# DL110.net
KiCad netlist of a schematic drawn in EAGLE
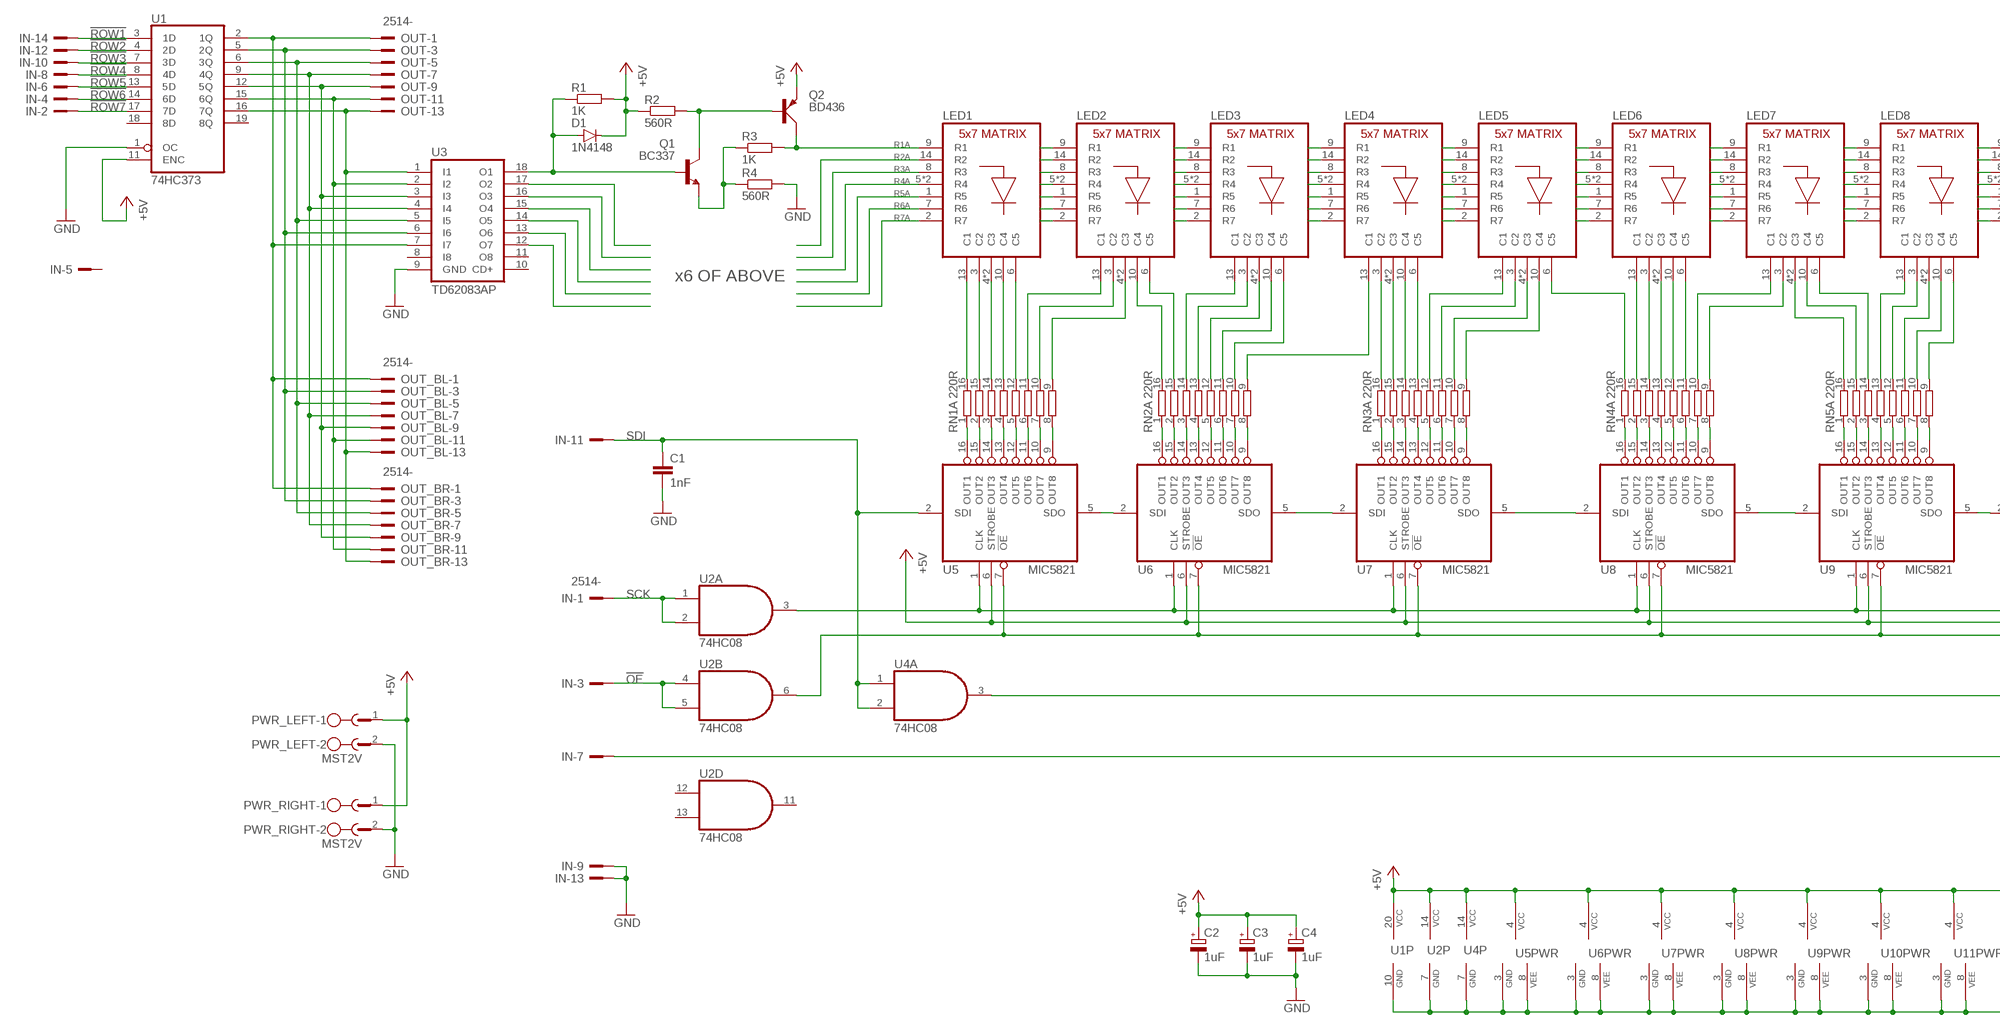
[diagram p0: schematic, sheet 1, part 1 of 2]
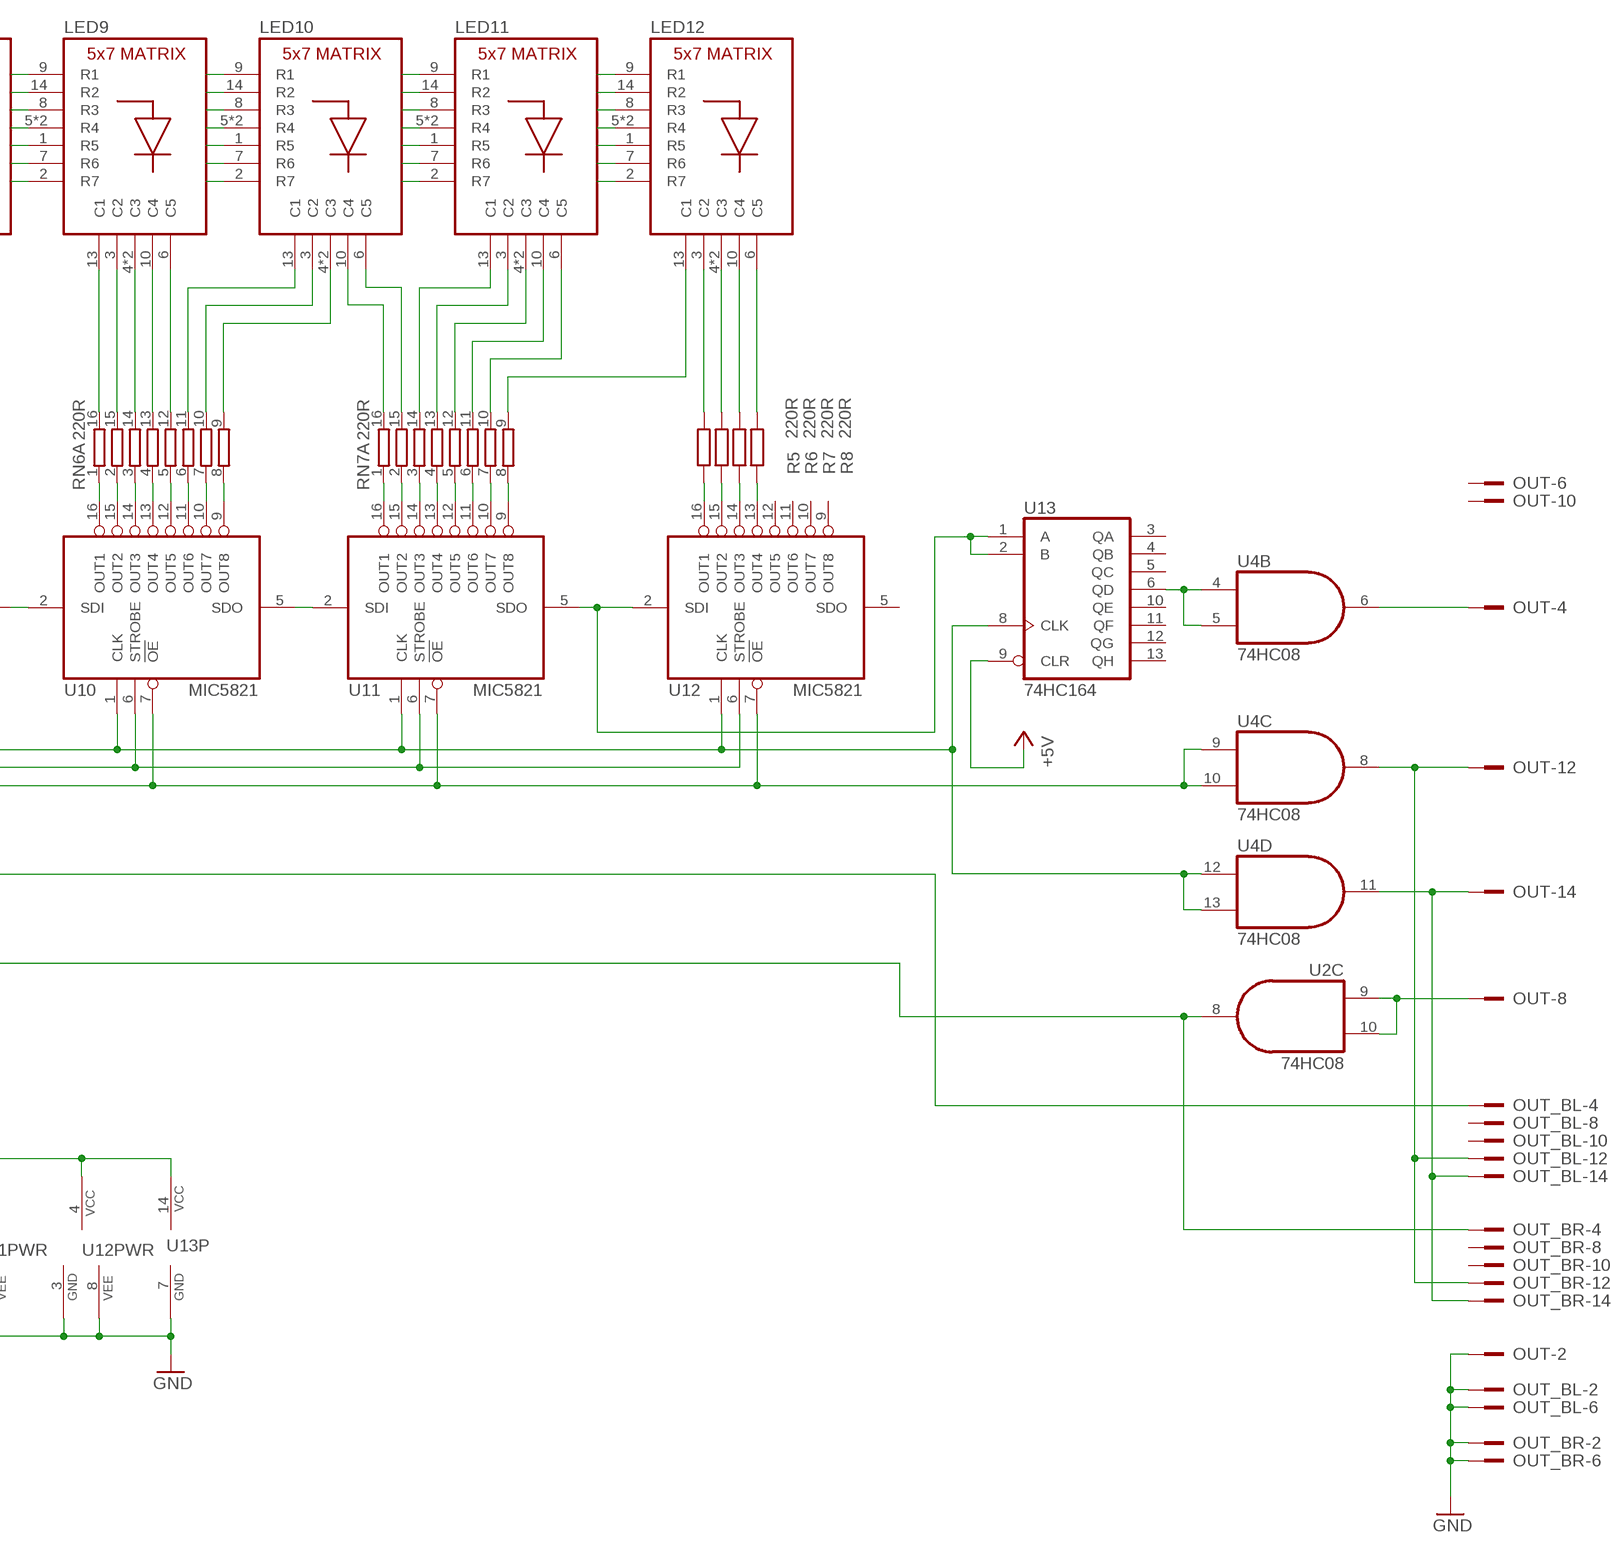
[diagram p1: schematic, sheet 1, part 2 of 2]

(export (version "E")
  (design (tool "Eeschema 10.0.6"))
  (components
    (comp (ref "C1")
      (value "1nF")
      (footprint "eagle-import:C050-025X075")
      (libsource (lib "eagle-import") (part "C-EU050-025X075"))
    )
    (comp (ref "C2")
      (value "1uF")
      (footprint "eagle-import:E2,5-5")
      (libsource (lib "eagle-import") (part "CPOL-EUE2.5-5"))
    )
    (comp (ref "C3")
      (value "1uF")
      (footprint "eagle-import:E2,5-5")
      (libsource (lib "eagle-import") (part "CPOL-EUE2.5-5"))
    )
    (comp (ref "C4")
      (value "1uF")
      (footprint "eagle-import:E2,5-5")
      (libsource (lib "eagle-import") (part "CPOL-EUE2.5-5"))
    )
    (comp (ref "D1")
      (value "1N4148")
      (footprint "eagle-import:DO35-10")
      (libsource (lib "eagle-import") (part "1N4148DO35-10"))
    )
    (comp (ref "IN")
      (value "2514-")
      (footprint "eagle-import:PAK100_2500-14")
      (libsource (lib "eagle-import") (part "2514-"))
    )
    (comp (ref "LED1")
      (value "CSM-57141")
      (footprint "eagle-import:CSM-57141")
      (libsource (lib "eagle-import") (part "CSM-57141"))
    )
    (comp (ref "LED2")
      (value "CSM-57141")
      (footprint "eagle-import:CSM-57141")
      (libsource (lib "eagle-import") (part "CSM-57141"))
    )
    (comp (ref "LED3")
      (value "CSM-57141")
      (footprint "eagle-import:CSM-57141")
      (libsource (lib "eagle-import") (part "CSM-57141"))
    )
    (comp (ref "LED4")
      (value "CSM-57141")
      (footprint "eagle-import:CSM-57141")
      (libsource (lib "eagle-import") (part "CSM-57141"))
    )
    (comp (ref "LED5")
      (value "CSM-57141")
      (footprint "eagle-import:CSM-57141")
      (libsource (lib "eagle-import") (part "CSM-57141"))
    )
    (comp (ref "LED6")
      (value "CSM-57141")
      (footprint "eagle-import:CSM-57141")
      (libsource (lib "eagle-import") (part "CSM-57141"))
    )
    (comp (ref "LED7")
      (value "CSM-57141")
      (footprint "eagle-import:CSM-57141")
      (libsource (lib "eagle-import") (part "CSM-57141"))
    )
    (comp (ref "LED8")
      (value "CSM-57141")
      (footprint "eagle-import:CSM-57141")
      (libsource (lib "eagle-import") (part "CSM-57141"))
    )
    (comp (ref "LED9")
      (value "CSM-57141")
      (footprint "eagle-import:CSM-57141")
      (libsource (lib "eagle-import") (part "CSM-57141"))
    )
    (comp (ref "LED10")
      (value "CSM-57141")
      (footprint "eagle-import:CSM-57141")
      (libsource (lib "eagle-import") (part "CSM-57141"))
    )
    (comp (ref "LED11")
      (value "CSM-57141")
      (footprint "eagle-import:CSM-57141")
      (libsource (lib "eagle-import") (part "CSM-57141"))
    )
    (comp (ref "LED12")
      (value "CSM-57141")
      (footprint "eagle-import:CSM-57141")
      (libsource (lib "eagle-import") (part "CSM-57141"))
    )
    (comp (ref "OUT")
      (value "2514-")
      (footprint "eagle-import:PAK100_2500-14")
      (fields (field (name "SPICEPREFIX") "X"))
      (libsource (lib "eagle-import") (part "2514-"))
    )
    (comp (ref "OUT_BL")
      (value "2514-")
      (footprint "eagle-import:PAK100_2500-14")
      (libsource (lib "eagle-import") (part "2514-"))
    )
    (comp (ref "OUT_BR")
      (value "2514-")
      (footprint "eagle-import:PAK100_2500-14")
      (libsource (lib "eagle-import") (part "2514-"))
    )
    (comp (ref "PWR_LEFT")
      (value "MST2V")
      (footprint "eagle-import:MSTBV2")
      (libsource (lib "eagle-import") (part "MST2V"))
    )
    (comp (ref "PWR_RIGHT")
      (value "MST2V")
      (footprint "eagle-import:MSTBV2")
      (libsource (lib "eagle-import") (part "MST2V"))
    )
    (comp (ref "Q1")
      (value "BC337")
      (footprint "eagle-import:TO92")
      (libsource (lib "eagle-import") (part "BC337"))
    )
    (comp (ref "Q2")
      (value "BD436")
      (footprint "eagle-import:TO126AV")
      (libsource (lib "eagle-import") (part "BD438"))
    )
    (comp (ref "R1")
      (value "1K")
      (footprint "eagle-import:0207_10")
      (libsource (lib "eagle-import") (part "R-EU_0207/10"))
    )
    (comp (ref "R2")
      (value "560R")
      (footprint "eagle-import:0207_10")
      (libsource (lib "eagle-import") (part "R-EU_0207/10"))
    )
    (comp (ref "R3")
      (value "1K")
      (footprint "eagle-import:0207_10")
      (libsource (lib "eagle-import") (part "R-EU_0207/10"))
    )
    (comp (ref "R4")
      (value "560R")
      (footprint "eagle-import:0207_10")
      (libsource (lib "eagle-import") (part "R-EU_0207/10"))
    )
    (comp (ref "R5")
      (value "220R")
      (footprint "eagle-import:0207_10")
      (libsource (lib "eagle-import") (part "R-EU_0207/10"))
    )
    (comp (ref "R6")
      (value "220R")
      (footprint "eagle-import:0207_10")
      (libsource (lib "eagle-import") (part "R-EU_0207/10"))
    )
    (comp (ref "R7")
      (value "220R")
      (footprint "eagle-import:0207_10")
      (libsource (lib "eagle-import") (part "R-EU_0207/10"))
    )
    (comp (ref "R8")
      (value "220R")
      (footprint "eagle-import:0207_10")
      (libsource (lib "eagle-import") (part "R-EU_0207/10"))
    )
    (comp (ref "RN1")
      (value "220R")
      (footprint "eagle-import:DIL16")
      (libsource (lib "eagle-import") (part "8R-N"))
    )
    (comp (ref "RN2")
      (value "220R")
      (footprint "eagle-import:DIL16")
      (libsource (lib "eagle-import") (part "8R-N"))
    )
    (comp (ref "RN3")
      (value "220R")
      (footprint "eagle-import:DIL16")
      (libsource (lib "eagle-import") (part "8R-N"))
    )
    (comp (ref "RN4")
      (value "220R")
      (footprint "eagle-import:DIL16")
      (libsource (lib "eagle-import") (part "8R-N"))
    )
    (comp (ref "RN5")
      (value "220R")
      (footprint "eagle-import:DIL16")
      (libsource (lib "eagle-import") (part "8R-N"))
    )
    (comp (ref "RN6")
      (value "220R")
      (footprint "eagle-import:DIL16")
      (libsource (lib "eagle-import") (part "8R-N"))
    )
    (comp (ref "RN7")
      (value "220R")
      (footprint "eagle-import:DIL16")
      (libsource (lib "eagle-import") (part "8R-N"))
    )
    (comp (ref "U1")
      (value "74HC373")
      (footprint "eagle-import:DIL20")
      (libsource (lib "eagle-import") (part "74373NLS"))
    )
    (comp (ref "U2")
      (value "74HC08")
      (footprint "eagle-import:DIL14")
      (libsource (lib "eagle-import") (part "7408NLS"))
    )
    (comp (ref "U3")
      (value "TD62083AP")
      (footprint "eagle-import:DIL18")
      (libsource (lib "eagle-import") (part "ULN2803A"))
    )
    (comp (ref "U4")
      (value "74HC08")
      (footprint "eagle-import:DIL14")
      (libsource (lib "eagle-import") (part "7408NLS"))
    )
    (comp (ref "U5")
      (value "MIC5821")
      (footprint "eagle-import:DIL16")
      (libsource (lib "eagle-import") (part "MIC5821BN"))
    )
    (comp (ref "U6")
      (value "MIC5821")
      (footprint "eagle-import:DIL16")
      (libsource (lib "eagle-import") (part "MIC5821BN"))
    )
    (comp (ref "U7")
      (value "MIC5821")
      (footprint "eagle-import:DIL16")
      (libsource (lib "eagle-import") (part "MIC5821BN"))
    )
    (comp (ref "U8")
      (value "MIC5821")
      (footprint "eagle-import:DIL16")
      (libsource (lib "eagle-import") (part "MIC5821BN"))
    )
    (comp (ref "U9")
      (value "MIC5821")
      (footprint "eagle-import:DIL16")
      (libsource (lib "eagle-import") (part "MIC5821BN"))
    )
    (comp (ref "U10")
      (value "MIC5821")
      (footprint "eagle-import:DIL16")
      (libsource (lib "eagle-import") (part "MIC5821BN"))
    )
    (comp (ref "U11")
      (value "MIC5821")
      (footprint "eagle-import:DIL16")
      (libsource (lib "eagle-import") (part "MIC5821BN"))
    )
    (comp (ref "U12")
      (value "MIC5821")
      (footprint "eagle-import:DIL16")
      (libsource (lib "eagle-import") (part "MIC5821BN"))
    )
    (comp (ref "U13")
      (value "74HC164")
      (footprint "eagle-import:DIL14")
      (libsource (lib "eagle-import") (part "74164NLS"))
    )
  )
  (nets
    (net (code "1") (name "+5V") (class "Default")
      (node (ref "C2") (pin "+") (pinfunction "+_+") (pintype "passive"))
      (node (ref "C3") (pin "+") (pinfunction "+_+") (pintype "passive"))
      (node (ref "C4") (pin "+") (pinfunction "+_+") (pintype "passive"))
      (node (ref "D1") (pin "C") (pinfunction "C_C") (pintype "passive"))
      (node (ref "PWR_LEFT") (pin "1") (pinfunction "1_1") (pintype "passive"))
      (node (ref "PWR_RIGHT") (pin "1") (pinfunction "1_1") (pintype "passive"))
      (node (ref "Q2") (pin "E") (pinfunction "E_E") (pintype "passive"))
      (node (ref "R1") (pin "2") (pinfunction "2_2") (pintype "passive"))
      (node (ref "R2") (pin "1") (pinfunction "1_1") (pintype "passive"))
      (node (ref "U1") (pin "11") (pinfunction "ENC_11") (pintype "input"))
      (node (ref "U1") (pin "20") (pinfunction "VCC_20") (pintype "power_in"))
      (node (ref "U10") (pin "4") (pinfunction "VCC_4") (pintype "power_in"))
      (node (ref "U10") (pin "6") (pinfunction "STROBE_6") (pintype "input"))
      (node (ref "U11") (pin "4") (pinfunction "VCC_4") (pintype "power_in"))
      (node (ref "U11") (pin "6") (pinfunction "STROBE_6") (pintype "input"))
      (node (ref "U12") (pin "4") (pinfunction "VCC_4") (pintype "power_in"))
      (node (ref "U12") (pin "6") (pinfunction "STROBE_6") (pintype "input"))
      (node (ref "U13") (pin "14") (pinfunction "VCC_14") (pintype "power_in"))
      (node (ref "U13") (pin "9") (pinfunction "CLR_9") (pintype "input"))
      (node (ref "U2") (pin "14") (pinfunction "VCC_14") (pintype "power_in"))
      (node (ref "U4") (pin "14") (pinfunction "VCC_14") (pintype "power_in"))
      (node (ref "U5") (pin "4") (pinfunction "VCC_4") (pintype "power_in"))
      (node (ref "U5") (pin "6") (pinfunction "STROBE_6") (pintype "input"))
      (node (ref "U6") (pin "4") (pinfunction "VCC_4") (pintype "power_in"))
      (node (ref "U6") (pin "6") (pinfunction "STROBE_6") (pintype "input"))
      (node (ref "U7") (pin "4") (pinfunction "VCC_4") (pintype "power_in"))
      (node (ref "U7") (pin "6") (pinfunction "STROBE_6") (pintype "input"))
      (node (ref "U8") (pin "4") (pinfunction "VCC_4") (pintype "power_in"))
      (node (ref "U8") (pin "6") (pinfunction "STROBE_6") (pintype "input"))
      (node (ref "U9") (pin "4") (pinfunction "VCC_4") (pintype "power_in"))
      (node (ref "U9") (pin "6") (pinfunction "STROBE_6") (pintype "input"))
    )
    (net (code "2") (name "/R1A") (class "Default")
      (node (ref "LED1") (pin "9") (pinfunction "R1_9") (pintype "input"))
      (node (ref "LED10") (pin "9") (pinfunction "R1_9") (pintype "input"))
      (node (ref "LED11") (pin "9") (pinfunction "R1_9") (pintype "input"))
      (node (ref "LED12") (pin "9") (pinfunction "R1_9") (pintype "input"))
      (node (ref "LED2") (pin "9") (pinfunction "R1_9") (pintype "input"))
      (node (ref "LED3") (pin "9") (pinfunction "R1_9") (pintype "input"))
      (node (ref "LED4") (pin "9") (pinfunction "R1_9") (pintype "input"))
      (node (ref "LED5") (pin "9") (pinfunction "R1_9") (pintype "input"))
      (node (ref "LED6") (pin "9") (pinfunction "R1_9") (pintype "input"))
      (node (ref "LED7") (pin "9") (pinfunction "R1_9") (pintype "input"))
      (node (ref "LED8") (pin "9") (pinfunction "R1_9") (pintype "input"))
      (node (ref "LED9") (pin "9") (pinfunction "R1_9") (pintype "input"))
      (node (ref "Q2") (pin "C") (pinfunction "C_C") (pintype "passive"))
      (node (ref "R3") (pin "2") (pinfunction "2_2") (pintype "passive"))
    )
    (net (code "3") (name "/R2A") (class "Default")
      (node (ref "LED1") (pin "14") (pinfunction "R2_14") (pintype "input"))
      (node (ref "LED10") (pin "14") (pinfunction "R2_14") (pintype "input"))
      (node (ref "LED11") (pin "14") (pinfunction "R2_14") (pintype "input"))
      (node (ref "LED12") (pin "14") (pinfunction "R2_14") (pintype "input"))
      (node (ref "LED2") (pin "14") (pinfunction "R2_14") (pintype "input"))
      (node (ref "LED3") (pin "14") (pinfunction "R2_14") (pintype "input"))
      (node (ref "LED4") (pin "14") (pinfunction "R2_14") (pintype "input"))
      (node (ref "LED5") (pin "14") (pinfunction "R2_14") (pintype "input"))
      (node (ref "LED6") (pin "14") (pinfunction "R2_14") (pintype "input"))
      (node (ref "LED7") (pin "14") (pinfunction "R2_14") (pintype "input"))
      (node (ref "LED8") (pin "14") (pinfunction "R2_14") (pintype "input"))
      (node (ref "LED9") (pin "14") (pinfunction "R2_14") (pintype "input"))
    )
    (net (code "4") (name "/R3A") (class "Default")
      (node (ref "LED1") (pin "8") (pinfunction "R3_8") (pintype "input"))
      (node (ref "LED10") (pin "8") (pinfunction "R3_8") (pintype "input"))
      (node (ref "LED11") (pin "8") (pinfunction "R3_8") (pintype "input"))
      (node (ref "LED12") (pin "8") (pinfunction "R3_8") (pintype "input"))
      (node (ref "LED2") (pin "8") (pinfunction "R3_8") (pintype "input"))
      (node (ref "LED3") (pin "8") (pinfunction "R3_8") (pintype "input"))
      (node (ref "LED4") (pin "8") (pinfunction "R3_8") (pintype "input"))
      (node (ref "LED5") (pin "8") (pinfunction "R3_8") (pintype "input"))
      (node (ref "LED6") (pin "8") (pinfunction "R3_8") (pintype "input"))
      (node (ref "LED7") (pin "8") (pinfunction "R3_8") (pintype "input"))
      (node (ref "LED8") (pin "8") (pinfunction "R3_8") (pintype "input"))
      (node (ref "LED9") (pin "8") (pinfunction "R3_8") (pintype "input"))
    )
    (net (code "5") (name "/R4A") (class "Default")
      (node (ref "LED1") (pin "12") (pinfunction "R4_12") (pintype "input"))
      (node (ref "LED1") (pin "5") (pinfunction "R4_5") (pintype "input"))
      (node (ref "LED10") (pin "12") (pinfunction "R4_12") (pintype "input"))
      (node (ref "LED10") (pin "5") (pinfunction "R4_5") (pintype "input"))
      (node (ref "LED11") (pin "12") (pinfunction "R4_12") (pintype "input"))
      (node (ref "LED11") (pin "5") (pinfunction "R4_5") (pintype "input"))
      (node (ref "LED12") (pin "12") (pinfunction "R4_12") (pintype "input"))
      (node (ref "LED12") (pin "5") (pinfunction "R4_5") (pintype "input"))
      (node (ref "LED2") (pin "12") (pinfunction "R4_12") (pintype "input"))
      (node (ref "LED2") (pin "5") (pinfunction "R4_5") (pintype "input"))
      (node (ref "LED3") (pin "12") (pinfunction "R4_12") (pintype "input"))
      (node (ref "LED3") (pin "5") (pinfunction "R4_5") (pintype "input"))
      (node (ref "LED4") (pin "12") (pinfunction "R4_12") (pintype "input"))
      (node (ref "LED4") (pin "5") (pinfunction "R4_5") (pintype "input"))
      (node (ref "LED5") (pin "12") (pinfunction "R4_12") (pintype "input"))
      (node (ref "LED5") (pin "5") (pinfunction "R4_5") (pintype "input"))
      (node (ref "LED6") (pin "12") (pinfunction "R4_12") (pintype "input"))
      (node (ref "LED6") (pin "5") (pinfunction "R4_5") (pintype "input"))
      (node (ref "LED7") (pin "12") (pinfunction "R4_12") (pintype "input"))
      (node (ref "LED7") (pin "5") (pinfunction "R4_5") (pintype "input"))
      (node (ref "LED8") (pin "12") (pinfunction "R4_12") (pintype "input"))
      (node (ref "LED8") (pin "5") (pinfunction "R4_5") (pintype "input"))
      (node (ref "LED9") (pin "12") (pinfunction "R4_12") (pintype "input"))
      (node (ref "LED9") (pin "5") (pinfunction "R4_5") (pintype "input"))
    )
    (net (code "6") (name "/R5A") (class "Default")
      (node (ref "LED1") (pin "1") (pinfunction "R5_1") (pintype "input"))
      (node (ref "LED10") (pin "1") (pinfunction "R5_1") (pintype "input"))
      (node (ref "LED11") (pin "1") (pinfunction "R5_1") (pintype "input"))
      (node (ref "LED12") (pin "1") (pinfunction "R5_1") (pintype "input"))
      (node (ref "LED2") (pin "1") (pinfunction "R5_1") (pintype "input"))
      (node (ref "LED3") (pin "1") (pinfunction "R5_1") (pintype "input"))
      (node (ref "LED4") (pin "1") (pinfunction "R5_1") (pintype "input"))
      (node (ref "LED5") (pin "1") (pinfunction "R5_1") (pintype "input"))
      (node (ref "LED6") (pin "1") (pinfunction "R5_1") (pintype "input"))
      (node (ref "LED7") (pin "1") (pinfunction "R5_1") (pintype "input"))
      (node (ref "LED8") (pin "1") (pinfunction "R5_1") (pintype "input"))
      (node (ref "LED9") (pin "1") (pinfunction "R5_1") (pintype "input"))
    )
    (net (code "7") (name "/R6A") (class "Default")
      (node (ref "LED1") (pin "7") (pinfunction "R6_7") (pintype "input"))
      (node (ref "LED10") (pin "7") (pinfunction "R6_7") (pintype "input"))
      (node (ref "LED11") (pin "7") (pinfunction "R6_7") (pintype "input"))
      (node (ref "LED12") (pin "7") (pinfunction "R6_7") (pintype "input"))
      (node (ref "LED2") (pin "7") (pinfunction "R6_7") (pintype "input"))
      (node (ref "LED3") (pin "7") (pinfunction "R6_7") (pintype "input"))
      (node (ref "LED4") (pin "7") (pinfunction "R6_7") (pintype "input"))
      (node (ref "LED5") (pin "7") (pinfunction "R6_7") (pintype "input"))
      (node (ref "LED6") (pin "7") (pinfunction "R6_7") (pintype "input"))
      (node (ref "LED7") (pin "7") (pinfunction "R6_7") (pintype "input"))
      (node (ref "LED8") (pin "7") (pinfunction "R6_7") (pintype "input"))
      (node (ref "LED9") (pin "7") (pinfunction "R6_7") (pintype "input"))
    )
    (net (code "8") (name "/R7A") (class "Default")
      (node (ref "LED1") (pin "2") (pinfunction "R7_2") (pintype "input"))
      (node (ref "LED10") (pin "2") (pinfunction "R7_2") (pintype "input"))
      (node (ref "LED11") (pin "2") (pinfunction "R7_2") (pintype "input"))
      (node (ref "LED12") (pin "2") (pinfunction "R7_2") (pintype "input"))
      (node (ref "LED2") (pin "2") (pinfunction "R7_2") (pintype "input"))
      (node (ref "LED3") (pin "2") (pinfunction "R7_2") (pintype "input"))
      (node (ref "LED4") (pin "2") (pinfunction "R7_2") (pintype "input"))
      (node (ref "LED5") (pin "2") (pinfunction "R7_2") (pintype "input"))
      (node (ref "LED6") (pin "2") (pinfunction "R7_2") (pintype "input"))
      (node (ref "LED7") (pin "2") (pinfunction "R7_2") (pintype "input"))
      (node (ref "LED8") (pin "2") (pinfunction "R7_2") (pintype "input"))
      (node (ref "LED9") (pin "2") (pinfunction "R7_2") (pintype "input"))
    )
    (net (code "9") (name "/SCK") (class "Default")
      (node (ref "IN") (pin "1") (pinfunction "KL_1") (pintype "passive"))
      (node (ref "U2") (pin "1") (pinfunction "I0_1") (pintype "input"))
      (node (ref "U2") (pin "2") (pinfunction "I1_2") (pintype "input"))
    )
    (net (code "10") (name "/SDI") (class "Default")
      (node (ref "C1") (pin "1") (pinfunction "1_1") (pintype "passive"))
      (node (ref "IN") (pin "11") (pinfunction "KL_11") (pintype "passive"))
      (node (ref "U4") (pin "1") (pinfunction "I0_1") (pintype "input"))
      (node (ref "U4") (pin "2") (pinfunction "I1_2") (pintype "input"))
      (node (ref "U5") (pin "2") (pinfunction "SDI_2") (pintype "input"))
    )
    (net (code "11") (name "/~{OE}") (class "Default")
      (node (ref "IN") (pin "3") (pinfunction "KL_3") (pintype "passive"))
      (node (ref "U2") (pin "4") (pinfunction "I0_4") (pintype "input"))
      (node (ref "U2") (pin "5") (pinfunction "I1_5") (pintype "input"))
    )
    (net (code "12") (name "/~{ROW1}") (class "Default")
      (node (ref "IN") (pin "14") (pinfunction "KL_14") (pintype "passive"))
      (node (ref "U1") (pin "3") (pinfunction "1D_3") (pintype "input"))
    )
    (net (code "13") (name "/~{ROW2}") (class "Default")
      (node (ref "IN") (pin "12") (pinfunction "KL_12") (pintype "passive"))
      (node (ref "U1") (pin "4") (pinfunction "2D_4") (pintype "input"))
    )
    (net (code "14") (name "/~{ROW3}") (class "Default")
      (node (ref "IN") (pin "10") (pinfunction "KL_10") (pintype "passive"))
      (node (ref "U1") (pin "7") (pinfunction "3D_7") (pintype "input"))
    )
    (net (code "15") (name "/~{ROW4}") (class "Default")
      (node (ref "IN") (pin "8") (pinfunction "KL_8") (pintype "passive"))
      (node (ref "U1") (pin "8") (pinfunction "4D_8") (pintype "input"))
    )
    (net (code "16") (name "/~{ROW5}") (class "Default")
      (node (ref "IN") (pin "6") (pinfunction "KL_6") (pintype "passive"))
      (node (ref "U1") (pin "13") (pinfunction "5D_13") (pintype "input"))
    )
    (net (code "17") (name "/~{ROW6}") (class "Default")
      (node (ref "IN") (pin "4") (pinfunction "KL_4") (pintype "passive"))
      (node (ref "U1") (pin "14") (pinfunction "6D_14") (pintype "input"))
    )
    (net (code "18") (name "/~{ROW7}") (class "Default")
      (node (ref "IN") (pin "2") (pinfunction "KL_2") (pintype "passive"))
      (node (ref "U1") (pin "17") (pinfunction "7D_17") (pintype "input"))
    )
    (net (code "19") (name "GND") (class "Default")
      (node (ref "C1") (pin "2") (pinfunction "2_2") (pintype "passive"))
      (node (ref "C2") (pin "-") (pinfunction "-_-") (pintype "passive"))
      (node (ref "C3") (pin "-") (pinfunction "-_-") (pintype "passive"))
      (node (ref "C4") (pin "-") (pinfunction "-_-") (pintype "passive"))
      (node (ref "IN") (pin "13") (pinfunction "KL_13") (pintype "passive"))
      (node (ref "IN") (pin "9") (pinfunction "KL_9") (pintype "passive"))
      (node (ref "OUT") (pin "2") (pinfunction "KL_2") (pintype "passive"))
      (node (ref "OUT_BL") (pin "2") (pinfunction "KL_2") (pintype "passive"))
      (node (ref "OUT_BL") (pin "6") (pinfunction "KL_6") (pintype "passive"))
      (node (ref "OUT_BR") (pin "2") (pinfunction "KL_2") (pintype "passive"))
      (node (ref "OUT_BR") (pin "6") (pinfunction "KL_6") (pintype "passive"))
      (node (ref "PWR_LEFT") (pin "2") (pinfunction "1_2") (pintype "passive"))
      (node (ref "PWR_RIGHT") (pin "2") (pinfunction "1_2") (pintype "passive"))
      (node (ref "R4") (pin "2") (pinfunction "2_2") (pintype "passive"))
      (node (ref "U1") (pin "1") (pinfunction "OC_1") (pintype "input"))
      (node (ref "U1") (pin "10") (pinfunction "GND_10") (pintype "power_in"))
      (node (ref "U10") (pin "3") (pinfunction "GND_3") (pintype "power_in"))
      (node (ref "U10") (pin "8") (pinfunction "VEE_8") (pintype "power_in"))
      (node (ref "U11") (pin "3") (pinfunction "GND_3") (pintype "power_in"))
      (node (ref "U11") (pin "8") (pinfunction "VEE_8") (pintype "power_in"))
      (node (ref "U12") (pin "3") (pinfunction "GND_3") (pintype "power_in"))
      (node (ref "U12") (pin "8") (pinfunction "VEE_8") (pintype "power_in"))
      (node (ref "U13") (pin "7") (pinfunction "GND_7") (pintype "power_in"))
      (node (ref "U2") (pin "7") (pinfunction "GND_7") (pintype "power_in"))
      (node (ref "U3") (pin "9") (pinfunction "GND_9") (pintype "power_in"))
      (node (ref "U4") (pin "7") (pinfunction "GND_7") (pintype "power_in"))
      (node (ref "U5") (pin "3") (pinfunction "GND_3") (pintype "power_in"))
      (node (ref "U5") (pin "8") (pinfunction "VEE_8") (pintype "power_in"))
      (node (ref "U6") (pin "3") (pinfunction "GND_3") (pintype "power_in"))
      (node (ref "U6") (pin "8") (pinfunction "VEE_8") (pintype "power_in"))
      (node (ref "U7") (pin "3") (pinfunction "GND_3") (pintype "power_in"))
      (node (ref "U7") (pin "8") (pinfunction "VEE_8") (pintype "power_in"))
      (node (ref "U8") (pin "3") (pinfunction "GND_3") (pintype "power_in"))
      (node (ref "U8") (pin "8") (pinfunction "VEE_8") (pintype "power_in"))
      (node (ref "U9") (pin "3") (pinfunction "GND_3") (pintype "power_in"))
      (node (ref "U9") (pin "8") (pinfunction "VEE_8") (pintype "power_in"))
    )
    (net (code "20") (name "Net-(INL-KL)") (class "Default")
      (node (ref "IN") (pin "7") (pinfunction "KL_7") (pintype "passive"))
      (node (ref "OUT_BR") (pin "4") (pinfunction "KL_4") (pintype "passive"))
      (node (ref "U2") (pin "8") (pinfunction "O_8") (pintype "output"))
    )
    (net (code "21") (name "Net-(LED1-C1)") (class "Default")
      (node (ref "LED1") (pin "13") (pinfunction "C1_13") (pintype "output"))
      (node (ref "RN1") (pin "16") (pinfunction "2_16") (pintype "passive"))
    )
    (net (code "22") (name "Net-(LED1-C2)") (class "Default")
      (node (ref "LED1") (pin "3") (pinfunction "C2_3") (pintype "output"))
      (node (ref "RN1") (pin "15") (pinfunction "2_15") (pintype "passive"))
    )
    (net (code "23") (name "Net-(LED1-C4)") (class "Default")
      (node (ref "LED1") (pin "10") (pinfunction "C4_10") (pintype "output"))
      (node (ref "RN1") (pin "13") (pinfunction "2_13") (pintype "passive"))
    )
    (net (code "24") (name "Net-(LED1-C5)") (class "Default")
      (node (ref "LED1") (pin "6") (pinfunction "C5_6") (pintype "output"))
      (node (ref "RN1") (pin "12") (pinfunction "2_12") (pintype "passive"))
    )
    (net (code "25") (name "Net-(LED2-C1)") (class "Default")
      (node (ref "LED2") (pin "13") (pinfunction "C1_13") (pintype "output"))
      (node (ref "RN1") (pin "11") (pinfunction "2_11") (pintype "passive"))
    )
    (net (code "26") (name "Net-(LED2-C2)") (class "Default")
      (node (ref "LED2") (pin "3") (pinfunction "C2_3") (pintype "output"))
      (node (ref "RN1") (pin "10") (pinfunction "2_10") (pintype "passive"))
    )
    (net (code "27") (name "Net-(LED2-C4)") (class "Default")
      (node (ref "LED2") (pin "10") (pinfunction "C4_10") (pintype "output"))
      (node (ref "RN2") (pin "16") (pinfunction "2_16") (pintype "passive"))
    )
    (net (code "28") (name "Net-(LED2-C5)") (class "Default")
      (node (ref "LED2") (pin "6") (pinfunction "C5_6") (pintype "output"))
      (node (ref "RN2") (pin "15") (pinfunction "2_15") (pintype "passive"))
    )
    (net (code "29") (name "Net-(LED3-C1)") (class "Default")
      (node (ref "LED3") (pin "13") (pinfunction "C1_13") (pintype "output"))
      (node (ref "RN2") (pin "14") (pinfunction "2_14") (pintype "passive"))
    )
    (net (code "30") (name "Net-(LED3-C2)") (class "Default")
      (node (ref "LED3") (pin "3") (pinfunction "C2_3") (pintype "output"))
      (node (ref "RN2") (pin "13") (pinfunction "2_13") (pintype "passive"))
    )
    (net (code "31") (name "Net-(LED3-C4)") (class "Default")
      (node (ref "LED3") (pin "10") (pinfunction "C4_10") (pintype "output"))
      (node (ref "RN2") (pin "11") (pinfunction "2_11") (pintype "passive"))
    )
    (net (code "32") (name "Net-(LED3-C5)") (class "Default")
      (node (ref "LED3") (pin "6") (pinfunction "C5_6") (pintype "output"))
      (node (ref "RN2") (pin "10") (pinfunction "2_10") (pintype "passive"))
    )
    (net (code "33") (name "Net-(LED4-C1)") (class "Default")
      (node (ref "LED4") (pin "13") (pinfunction "C1_13") (pintype "output"))
      (node (ref "RN2") (pin "9") (pinfunction "2_9") (pintype "passive"))
    )
    (net (code "34") (name "Net-(LED4-C2)") (class "Default")
      (node (ref "LED4") (pin "3") (pinfunction "C2_3") (pintype "output"))
      (node (ref "RN3") (pin "16") (pinfunction "2_16") (pintype "passive"))
    )
    (net (code "35") (name "Net-(LED4-C4)") (class "Default")
      (node (ref "LED4") (pin "10") (pinfunction "C4_10") (pintype "output"))
      (node (ref "RN3") (pin "14") (pinfunction "2_14") (pintype "passive"))
    )
    (net (code "36") (name "Net-(LED4-C5)") (class "Default")
      (node (ref "LED4") (pin "6") (pinfunction "C5_6") (pintype "output"))
      (node (ref "RN3") (pin "13") (pinfunction "2_13") (pintype "passive"))
    )
    (net (code "37") (name "Net-(LED5-C1)") (class "Default")
      (node (ref "LED5") (pin "13") (pinfunction "C1_13") (pintype "output"))
      (node (ref "RN3") (pin "12") (pinfunction "2_12") (pintype "passive"))
    )
    (net (code "38") (name "Net-(LED5-C2)") (class "Default")
      (node (ref "LED5") (pin "3") (pinfunction "C2_3") (pintype "output"))
      (node (ref "RN3") (pin "11") (pinfunction "2_11") (pintype "passive"))
    )
    (net (code "39") (name "Net-(LED5-C4)") (class "Default")
      (node (ref "LED5") (pin "10") (pinfunction "C4_10") (pintype "output"))
      (node (ref "RN3") (pin "9") (pinfunction "2_9") (pintype "passive"))
    )
    (net (code "40") (name "Net-(LED5-C5)") (class "Default")
      (node (ref "LED5") (pin "6") (pinfunction "C5_6") (pintype "output"))
      (node (ref "RN4") (pin "16") (pinfunction "2_16") (pintype "passive"))
    )
    (net (code "41") (name "Net-(LED6-C1)") (class "Default")
      (node (ref "LED6") (pin "13") (pinfunction "C1_13") (pintype "output"))
      (node (ref "RN4") (pin "15") (pinfunction "2_15") (pintype "passive"))
    )
    (net (code "42") (name "Net-(LED6-C2)") (class "Default")
      (node (ref "LED6") (pin "3") (pinfunction "C2_3") (pintype "output"))
      (node (ref "RN4") (pin "14") (pinfunction "2_14") (pintype "passive"))
    )
    (net (code "43") (name "Net-(LED6-C4)") (class "Default")
      (node (ref "LED6") (pin "10") (pinfunction "C4_10") (pintype "output"))
      (node (ref "RN4") (pin "12") (pinfunction "2_12") (pintype "passive"))
    )
    (net (code "44") (name "Net-(LED6-C5)") (class "Default")
      (node (ref "LED6") (pin "6") (pinfunction "C5_6") (pintype "output"))
      (node (ref "RN4") (pin "11") (pinfunction "2_11") (pintype "passive"))
    )
    (net (code "45") (name "Net-(LED7-C1)") (class "Default")
      (node (ref "LED7") (pin "13") (pinfunction "C1_13") (pintype "output"))
      (node (ref "RN4") (pin "10") (pinfunction "2_10") (pintype "passive"))
    )
    (net (code "46") (name "Net-(LED7-C2)") (class "Default")
      (node (ref "LED7") (pin "3") (pinfunction "C2_3") (pintype "output"))
      (node (ref "RN4") (pin "9") (pinfunction "2_9") (pintype "passive"))
    )
    (net (code "47") (name "Net-(LED7-C4)") (class "Default")
      (node (ref "LED7") (pin "10") (pinfunction "C4_10") (pintype "output"))
      (node (ref "RN5") (pin "15") (pinfunction "2_15") (pintype "passive"))
    )
    (net (code "48") (name "Net-(LED7-C5)") (class "Default")
      (node (ref "LED7") (pin "6") (pinfunction "C5_6") (pintype "output"))
      (node (ref "RN5") (pin "14") (pinfunction "2_14") (pintype "passive"))
    )
    (net (code "49") (name "Net-(LED8-C1)") (class "Default")
      (node (ref "LED8") (pin "13") (pinfunction "C1_13") (pintype "output"))
      (node (ref "RN5") (pin "13") (pinfunction "2_13") (pintype "passive"))
    )
    (net (code "50") (name "Net-(LED8-C2)") (class "Default")
      (node (ref "LED8") (pin "3") (pinfunction "C2_3") (pintype "output"))
      (node (ref "RN5") (pin "12") (pinfunction "2_12") (pintype "passive"))
    )
    (net (code "51") (name "Net-(LED8-C4)") (class "Default")
      (node (ref "LED8") (pin "10") (pinfunction "C4_10") (pintype "output"))
      (node (ref "RN5") (pin "10") (pinfunction "2_10") (pintype "passive"))
    )
    (net (code "52") (name "Net-(LED8-C5)") (class "Default")
      (node (ref "LED8") (pin "6") (pinfunction "C5_6") (pintype "output"))
      (node (ref "RN5") (pin "9") (pinfunction "2_9") (pintype "passive"))
    )
    (net (code "53") (name "Net-(LED9-C1)") (class "Default")
      (node (ref "LED9") (pin "13") (pinfunction "C1_13") (pintype "output"))
      (node (ref "RN6") (pin "16") (pinfunction "2_16") (pintype "passive"))
    )
    (net (code "54") (name "Net-(LED9-C2)") (class "Default")
      (node (ref "LED9") (pin "3") (pinfunction "C2_3") (pintype "output"))
      (node (ref "RN6") (pin "15") (pinfunction "2_15") (pintype "passive"))
    )
    (net (code "55") (name "Net-(LED9-C4)") (class "Default")
      (node (ref "LED9") (pin "10") (pinfunction "C4_10") (pintype "output"))
      (node (ref "RN6") (pin "13") (pinfunction "2_13") (pintype "passive"))
    )
    (net (code "56") (name "Net-(LED9-C5)") (class "Default")
      (node (ref "LED9") (pin "6") (pinfunction "C5_6") (pintype "output"))
      (node (ref "RN6") (pin "12") (pinfunction "2_12") (pintype "passive"))
    )
    (net (code "57") (name "Net-(LED10-C1)") (class "Default")
      (node (ref "LED10") (pin "13") (pinfunction "C1_13") (pintype "output"))
      (node (ref "RN6") (pin "11") (pinfunction "2_11") (pintype "passive"))
    )
    (net (code "58") (name "Net-(LED10-C2)") (class "Default")
      (node (ref "LED10") (pin "3") (pinfunction "C2_3") (pintype "output"))
      (node (ref "RN6") (pin "10") (pinfunction "2_10") (pintype "passive"))
    )
    (net (code "59") (name "Net-(LED10-C4)") (class "Default")
      (node (ref "LED10") (pin "10") (pinfunction "C4_10") (pintype "output"))
      (node (ref "RN7") (pin "16") (pinfunction "2_16") (pintype "passive"))
    )
    (net (code "60") (name "Net-(LED10-C5)") (class "Default")
      (node (ref "LED10") (pin "6") (pinfunction "C5_6") (pintype "output"))
      (node (ref "RN7") (pin "15") (pinfunction "2_15") (pintype "passive"))
    )
    (net (code "61") (name "Net-(LED11-C1)") (class "Default")
      (node (ref "LED11") (pin "13") (pinfunction "C1_13") (pintype "output"))
      (node (ref "RN7") (pin "14") (pinfunction "2_14") (pintype "passive"))
    )
    (net (code "62") (name "Net-(LED11-C2)") (class "Default")
      (node (ref "LED11") (pin "3") (pinfunction "C2_3") (pintype "output"))
      (node (ref "RN7") (pin "13") (pinfunction "2_13") (pintype "passive"))
    )
    (net (code "63") (name "Net-(LED11-C4)") (class "Default")
      (node (ref "LED11") (pin "10") (pinfunction "C4_10") (pintype "output"))
      (node (ref "RN7") (pin "11") (pinfunction "2_11") (pintype "passive"))
    )
    (net (code "64") (name "Net-(LED11-C5)") (class "Default")
      (node (ref "LED11") (pin "6") (pinfunction "C5_6") (pintype "output"))
      (node (ref "RN7") (pin "10") (pinfunction "2_10") (pintype "passive"))
    )
    (net (code "65") (name "Net-(LED12-C1)") (class "Default")
      (node (ref "LED12") (pin "13") (pinfunction "C1_13") (pintype "output"))
      (node (ref "RN7") (pin "9") (pinfunction "2_9") (pintype "passive"))
    )
    (net (code "66") (name "Net-(LED12-C2)") (class "Default")
      (node (ref "LED12") (pin "3") (pinfunction "C2_3") (pintype "output"))
      (node (ref "R5") (pin "2") (pinfunction "2_2") (pintype "passive"))
    )
    (net (code "67") (name "Net-(LED12-C3-Pad11)") (class "Default")
      (node (ref "LED12") (pin "11") (pinfunction "C3_11") (pintype "output"))
      (node (ref "LED12") (pin "4") (pinfunction "C3_4") (pintype "output"))
      (node (ref "R6") (pin "2") (pinfunction "2_2") (pintype "passive"))
    )
    (net (code "68") (name "Net-(LED12-C4)") (class "Default")
      (node (ref "LED12") (pin "10") (pinfunction "C4_10") (pintype "output"))
      (node (ref "R7") (pin "2") (pinfunction "2_2") (pintype "passive"))
    )
    (net (code "69") (name "Net-(LED12-C5)") (class "Default")
      (node (ref "LED12") (pin "6") (pinfunction "C5_6") (pintype "output"))
      (node (ref "R8") (pin "2") (pinfunction "2_2") (pintype "passive"))
    )
    (net (code "70") (name "Net-(OUTA-KL)") (class "Default")
      (node (ref "OUT") (pin "1") (pinfunction "KL_1") (pintype "passive"))
      (node (ref "OUT_BL") (pin "1") (pinfunction "KL_1") (pintype "passive"))
      (node (ref "OUT_BR") (pin "1") (pinfunction "KL_1") (pintype "passive"))
      (node (ref "U1") (pin "2") (pinfunction "1Q_2") (pintype "tri_state"))
      (node (ref "U3") (pin "7") (pinfunction "I7_7") (pintype "input"))
    )
    (net (code "71") (name "Net-(OUTC-KL)") (class "Default")
      (node (ref "OUT") (pin "11") (pinfunction "KL_11") (pintype "passive"))
      (node (ref "OUT_BL") (pin "11") (pinfunction "KL_11") (pintype "passive"))
      (node (ref "OUT_BR") (pin "11") (pinfunction "KL_11") (pintype "passive"))
      (node (ref "U1") (pin "15") (pinfunction "6Q_15") (pintype "tri_state"))
      (node (ref "U3") (pin "2") (pinfunction "I2_2") (pintype "input"))
    )
    (net (code "72") (name "Net-(OUTD-KL)") (class "Default")
      (node (ref "OUT") (pin "12") (pinfunction "KL_12") (pintype "passive"))
      (node (ref "OUT_BL") (pin "12") (pinfunction "KL_12") (pintype "passive"))
      (node (ref "OUT_BR") (pin "12") (pinfunction "KL_12") (pintype "passive"))
      (node (ref "U4") (pin "8") (pinfunction "O_8") (pintype "output"))
    )
    (net (code "73") (name "Net-(OUTE-KL)") (class "Default")
      (node (ref "OUT") (pin "13") (pinfunction "KL_13") (pintype "passive"))
      (node (ref "OUT_BL") (pin "13") (pinfunction "KL_13") (pintype "passive"))
      (node (ref "OUT_BR") (pin "13") (pinfunction "KL_13") (pintype "passive"))
      (node (ref "U1") (pin "16") (pinfunction "7Q_16") (pintype "tri_state"))
      (node (ref "U3") (pin "1") (pinfunction "I1_1") (pintype "input"))
    )
    (net (code "74") (name "Net-(OUTF-KL)") (class "Default")
      (node (ref "OUT") (pin "14") (pinfunction "KL_14") (pintype "passive"))
      (node (ref "OUT_BL") (pin "14") (pinfunction "KL_14") (pintype "passive"))
      (node (ref "OUT_BR") (pin "14") (pinfunction "KL_14") (pintype "passive"))
      (node (ref "U4") (pin "11") (pinfunction "O_11") (pintype "output"))
    )
    (net (code "75") (name "Net-(OUTH-KL)") (class "Default")
      (node (ref "OUT") (pin "3") (pinfunction "KL_3") (pintype "passive"))
      (node (ref "OUT_BL") (pin "3") (pinfunction "KL_3") (pintype "passive"))
      (node (ref "OUT_BR") (pin "3") (pinfunction "KL_3") (pintype "passive"))
      (node (ref "U1") (pin "5") (pinfunction "2Q_5") (pintype "tri_state"))
      (node (ref "U3") (pin "6") (pinfunction "I6_6") (pintype "input"))
    )
    (net (code "76") (name "Net-(OUTI-KL)") (class "Default")
      (node (ref "OUT") (pin "4") (pinfunction "KL_4") (pintype "passive"))
      (node (ref "U4") (pin "6") (pinfunction "O_6") (pintype "output"))
    )
    (net (code "77") (name "Net-(OUTJ-KL)") (class "Default")
      (node (ref "OUT") (pin "5") (pinfunction "KL_5") (pintype "passive"))
      (node (ref "OUT_BL") (pin "5") (pinfunction "KL_5") (pintype "passive"))
      (node (ref "OUT_BR") (pin "5") (pinfunction "KL_5") (pintype "passive"))
      (node (ref "U1") (pin "6") (pinfunction "3Q_6") (pintype "tri_state"))
      (node (ref "U3") (pin "5") (pinfunction "I5_5") (pintype "input"))
    )
    (net (code "78") (name "Net-(OUTL-KL)") (class "Default")
      (node (ref "OUT") (pin "7") (pinfunction "KL_7") (pintype "passive"))
      (node (ref "OUT_BL") (pin "7") (pinfunction "KL_7") (pintype "passive"))
      (node (ref "OUT_BR") (pin "7") (pinfunction "KL_7") (pintype "passive"))
      (node (ref "U1") (pin "9") (pinfunction "4Q_9") (pintype "tri_state"))
      (node (ref "U3") (pin "4") (pinfunction "I4_4") (pintype "input"))
    )
    (net (code "79") (name "Net-(OUTM-KL)") (class "Default")
      (node (ref "OUT") (pin "8") (pinfunction "KL_8") (pintype "passive"))
      (node (ref "U2") (pin "10") (pinfunction "I1_10") (pintype "input"))
      (node (ref "U2") (pin "9") (pinfunction "I0_9") (pintype "input"))
    )
    (net (code "80") (name "Net-(OUTN-KL)") (class "Default")
      (node (ref "OUT") (pin "9") (pinfunction "KL_9") (pintype "passive"))
      (node (ref "OUT_BL") (pin "9") (pinfunction "KL_9") (pintype "passive"))
      (node (ref "OUT_BR") (pin "9") (pinfunction "KL_9") (pintype "passive"))
      (node (ref "U1") (pin "12") (pinfunction "5Q_12") (pintype "tri_state"))
      (node (ref "U3") (pin "3") (pinfunction "I3_3") (pintype "input"))
    )
    (net (code "81") (name "Net-(OUT_BLI-KL)") (class "Default")
      (node (ref "OUT_BL") (pin "4") (pinfunction "KL_4") (pintype "passive"))
      (node (ref "U4") (pin "3") (pinfunction "O_3") (pintype "output"))
    )
    (net (code "82") (name "Net-(Q1-B)") (class "Default")
      (node (ref "D1") (pin "A") (pinfunction "A_A") (pintype "passive"))
      (node (ref "Q1") (pin "2") (pinfunction "B_2") (pintype "passive"))
      (node (ref "R1") (pin "1") (pinfunction "1_1") (pintype "passive"))
      (node (ref "U3") (pin "18") (pinfunction "O1_18") (pintype "open_collector"))
    )
    (net (code "83") (name "Net-(Q1-C)") (class "Default")
      (node (ref "Q1") (pin "3") (pinfunction "C_3") (pintype "passive"))
      (node (ref "Q2") (pin "B") (pinfunction "B_B") (pintype "passive"))
      (node (ref "R2") (pin "2") (pinfunction "2_2") (pintype "passive"))
    )
    (net (code "84") (name "Net-(Q1-E)") (class "Default")
      (node (ref "Q1") (pin "1") (pinfunction "E_1") (pintype "passive"))
      (node (ref "R3") (pin "1") (pinfunction "1_1") (pintype "passive"))
      (node (ref "R4") (pin "1") (pinfunction "1_1") (pintype "passive"))
    )
    (net (code "85") (name "Net-(RN1B-1)") (class "Default")
      (node (ref "RN1") (pin "2") (pinfunction "1_2") (pintype "passive"))
      (node (ref "U5") (pin "15") (pinfunction "OUT2_15") (pintype "open_collector"))
    )
    (net (code "86") (name "Net-(RN1C-1)") (class "Default")
      (node (ref "RN1") (pin "3") (pinfunction "1_3") (pintype "passive"))
      (node (ref "U5") (pin "14") (pinfunction "OUT3_14") (pintype "open_collector"))
    )
    (net (code "87") (name "Net-(RN1C-2)") (class "Default")
      (node (ref "LED1") (pin "11") (pinfunction "C3_11") (pintype "output"))
      (node (ref "LED1") (pin "4") (pinfunction "C3_4") (pintype "output"))
      (node (ref "RN1") (pin "14") (pinfunction "2_14") (pintype "passive"))
    )
    (net (code "88") (name "Net-(RN1D-1)") (class "Default")
      (node (ref "RN1") (pin "4") (pinfunction "1_4") (pintype "passive"))
      (node (ref "U5") (pin "13") (pinfunction "OUT4_13") (pintype "open_collector"))
    )
    (net (code "89") (name "Net-(RN1E-1)") (class "Default")
      (node (ref "RN1") (pin "5") (pinfunction "1_5") (pintype "passive"))
      (node (ref "U5") (pin "12") (pinfunction "OUT5_12") (pintype "open_collector"))
    )
    (net (code "90") (name "Net-(RN1F-1)") (class "Default")
      (node (ref "RN1") (pin "6") (pinfunction "1_6") (pintype "passive"))
      (node (ref "U5") (pin "11") (pinfunction "OUT6_11") (pintype "open_collector"))
    )
    (net (code "91") (name "Net-(RN1G-1)") (class "Default")
      (node (ref "RN1") (pin "7") (pinfunction "1_7") (pintype "passive"))
      (node (ref "U5") (pin "10") (pinfunction "OUT7_10") (pintype "open_collector"))
    )
    (net (code "92") (name "Net-(RN1H-1)") (class "Default")
      (node (ref "RN1") (pin "8") (pinfunction "1_8") (pintype "passive"))
      (node (ref "U5") (pin "9") (pinfunction "OUT8_9") (pintype "open_collector"))
    )
    (net (code "93") (name "Net-(RN1H-2)") (class "Default")
      (node (ref "LED2") (pin "11") (pinfunction "C3_11") (pintype "output"))
      (node (ref "LED2") (pin "4") (pinfunction "C3_4") (pintype "output"))
      (node (ref "RN1") (pin "9") (pinfunction "2_9") (pintype "passive"))
    )
    (net (code "94") (name "Net-(RN2B-1)") (class "Default")
      (node (ref "RN2") (pin "2") (pinfunction "1_2") (pintype "passive"))
      (node (ref "U6") (pin "15") (pinfunction "OUT2_15") (pintype "open_collector"))
    )
    (net (code "95") (name "Net-(RN2C-1)") (class "Default")
      (node (ref "RN2") (pin "3") (pinfunction "1_3") (pintype "passive"))
      (node (ref "U6") (pin "14") (pinfunction "OUT3_14") (pintype "open_collector"))
    )
    (net (code "96") (name "Net-(RN2D-1)") (class "Default")
      (node (ref "RN2") (pin "4") (pinfunction "1_4") (pintype "passive"))
      (node (ref "U6") (pin "13") (pinfunction "OUT4_13") (pintype "open_collector"))
    )
    (net (code "97") (name "Net-(RN2E-1)") (class "Default")
      (node (ref "RN2") (pin "5") (pinfunction "1_5") (pintype "passive"))
      (node (ref "U6") (pin "12") (pinfunction "OUT5_12") (pintype "open_collector"))
    )
    (net (code "98") (name "Net-(RN2E-2)") (class "Default")
      (node (ref "LED3") (pin "11") (pinfunction "C3_11") (pintype "output"))
      (node (ref "LED3") (pin "4") (pinfunction "C3_4") (pintype "output"))
      (node (ref "RN2") (pin "12") (pinfunction "2_12") (pintype "passive"))
    )
    (net (code "99") (name "Net-(RN2F-1)") (class "Default")
      (node (ref "RN2") (pin "6") (pinfunction "1_6") (pintype "passive"))
      (node (ref "U6") (pin "11") (pinfunction "OUT6_11") (pintype "open_collector"))
    )
    (net (code "100") (name "Net-(RN2G-1)") (class "Default")
      (node (ref "RN2") (pin "7") (pinfunction "1_7") (pintype "passive"))
      (node (ref "U6") (pin "10") (pinfunction "OUT7_10") (pintype "open_collector"))
    )
    (net (code "101") (name "Net-(RN2H-1)") (class "Default")
      (node (ref "RN2") (pin "8") (pinfunction "1_8") (pintype "passive"))
      (node (ref "U6") (pin "9") (pinfunction "OUT8_9") (pintype "open_collector"))
    )
    (net (code "102") (name "Net-(RN3B-1)") (class "Default")
      (node (ref "RN3") (pin "2") (pinfunction "1_2") (pintype "passive"))
      (node (ref "U7") (pin "15") (pinfunction "OUT2_15") (pintype "open_collector"))
    )
    (net (code "103") (name "Net-(RN3B-2)") (class "Default")
      (node (ref "LED4") (pin "11") (pinfunction "C3_11") (pintype "output"))
      (node (ref "LED4") (pin "4") (pinfunction "C3_4") (pintype "output"))
      (node (ref "RN3") (pin "15") (pinfunction "2_15") (pintype "passive"))
    )
    (net (code "104") (name "Net-(RN3C-1)") (class "Default")
      (node (ref "RN3") (pin "3") (pinfunction "1_3") (pintype "passive"))
      (node (ref "U7") (pin "14") (pinfunction "OUT3_14") (pintype "open_collector"))
    )
    (net (code "105") (name "Net-(RN3D-1)") (class "Default")
      (node (ref "RN3") (pin "4") (pinfunction "1_4") (pintype "passive"))
      (node (ref "U7") (pin "13") (pinfunction "OUT4_13") (pintype "open_collector"))
    )
    (net (code "106") (name "Net-(RN3E-1)") (class "Default")
      (node (ref "RN3") (pin "5") (pinfunction "1_5") (pintype "passive"))
      (node (ref "U7") (pin "12") (pinfunction "OUT5_12") (pintype "open_collector"))
    )
    (net (code "107") (name "Net-(RN3F-1)") (class "Default")
      (node (ref "RN3") (pin "6") (pinfunction "1_6") (pintype "passive"))
      (node (ref "U7") (pin "11") (pinfunction "OUT6_11") (pintype "open_collector"))
    )
    (net (code "108") (name "Net-(RN3G-1)") (class "Default")
      (node (ref "RN3") (pin "7") (pinfunction "1_7") (pintype "passive"))
      (node (ref "U7") (pin "10") (pinfunction "OUT7_10") (pintype "open_collector"))
    )
    (net (code "109") (name "Net-(RN3G-2)") (class "Default")
      (node (ref "LED5") (pin "11") (pinfunction "C3_11") (pintype "output"))
      (node (ref "LED5") (pin "4") (pinfunction "C3_4") (pintype "output"))
      (node (ref "RN3") (pin "10") (pinfunction "2_10") (pintype "passive"))
    )
    (net (code "110") (name "Net-(RN3H-1)") (class "Default")
      (node (ref "RN3") (pin "8") (pinfunction "1_8") (pintype "passive"))
      (node (ref "U7") (pin "9") (pinfunction "OUT8_9") (pintype "open_collector"))
    )
    (net (code "111") (name "Net-(RN4B-1)") (class "Default")
      (node (ref "RN4") (pin "2") (pinfunction "1_2") (pintype "passive"))
      (node (ref "U8") (pin "15") (pinfunction "OUT2_15") (pintype "open_collector"))
    )
    (net (code "112") (name "Net-(RN4C-1)") (class "Default")
      (node (ref "RN4") (pin "3") (pinfunction "1_3") (pintype "passive"))
      (node (ref "U8") (pin "14") (pinfunction "OUT3_14") (pintype "open_collector"))
    )
    (net (code "113") (name "Net-(RN4D-1)") (class "Default")
      (node (ref "RN4") (pin "4") (pinfunction "1_4") (pintype "passive"))
      (node (ref "U8") (pin "13") (pinfunction "OUT4_13") (pintype "open_collector"))
    )
    (net (code "114") (name "Net-(RN4D-2)") (class "Default")
      (node (ref "LED6") (pin "11") (pinfunction "C3_11") (pintype "output"))
      (node (ref "LED6") (pin "4") (pinfunction "C3_4") (pintype "output"))
      (node (ref "RN4") (pin "13") (pinfunction "2_13") (pintype "passive"))
    )
    (net (code "115") (name "Net-(RN4E-1)") (class "Default")
      (node (ref "RN4") (pin "5") (pinfunction "1_5") (pintype "passive"))
      (node (ref "U8") (pin "12") (pinfunction "OUT5_12") (pintype "open_collector"))
    )
    (net (code "116") (name "Net-(RN4F-1)") (class "Default")
      (node (ref "RN4") (pin "6") (pinfunction "1_6") (pintype "passive"))
      (node (ref "U8") (pin "11") (pinfunction "OUT6_11") (pintype "open_collector"))
    )
    (net (code "117") (name "Net-(RN4G-1)") (class "Default")
      (node (ref "RN4") (pin "7") (pinfunction "1_7") (pintype "passive"))
      (node (ref "U8") (pin "10") (pinfunction "OUT7_10") (pintype "open_collector"))
    )
    (net (code "118") (name "Net-(RN4H-1)") (class "Default")
      (node (ref "RN4") (pin "8") (pinfunction "1_8") (pintype "passive"))
      (node (ref "U8") (pin "9") (pinfunction "OUT8_9") (pintype "open_collector"))
    )
    (net (code "119") (name "Net-(RN5A-2)") (class "Default")
      (node (ref "LED7") (pin "11") (pinfunction "C3_11") (pintype "output"))
      (node (ref "LED7") (pin "4") (pinfunction "C3_4") (pintype "output"))
      (node (ref "RN5") (pin "16") (pinfunction "2_16") (pintype "passive"))
    )
    (net (code "120") (name "Net-(RN5B-1)") (class "Default")
      (node (ref "RN5") (pin "2") (pinfunction "1_2") (pintype "passive"))
      (node (ref "U9") (pin "15") (pinfunction "OUT2_15") (pintype "open_collector"))
    )
    (net (code "121") (name "Net-(RN5C-1)") (class "Default")
      (node (ref "RN5") (pin "3") (pinfunction "1_3") (pintype "passive"))
      (node (ref "U9") (pin "14") (pinfunction "OUT3_14") (pintype "open_collector"))
    )
    (net (code "122") (name "Net-(RN5D-1)") (class "Default")
      (node (ref "RN5") (pin "4") (pinfunction "1_4") (pintype "passive"))
      (node (ref "U9") (pin "13") (pinfunction "OUT4_13") (pintype "open_collector"))
    )
    (net (code "123") (name "Net-(RN5E-1)") (class "Default")
      (node (ref "RN5") (pin "5") (pinfunction "1_5") (pintype "passive"))
      (node (ref "U9") (pin "12") (pinfunction "OUT5_12") (pintype "open_collector"))
    )
    (net (code "124") (name "Net-(RN5F-1)") (class "Default")
      (node (ref "RN5") (pin "6") (pinfunction "1_6") (pintype "passive"))
      (node (ref "U9") (pin "11") (pinfunction "OUT6_11") (pintype "open_collector"))
    )
    (net (code "125") (name "Net-(RN5F-2)") (class "Default")
      (node (ref "LED8") (pin "11") (pinfunction "C3_11") (pintype "output"))
      (node (ref "LED8") (pin "4") (pinfunction "C3_4") (pintype "output"))
      (node (ref "RN5") (pin "11") (pinfunction "2_11") (pintype "passive"))
    )
    (net (code "126") (name "Net-(RN5G-1)") (class "Default")
      (node (ref "RN5") (pin "7") (pinfunction "1_7") (pintype "passive"))
      (node (ref "U9") (pin "10") (pinfunction "OUT7_10") (pintype "open_collector"))
    )
    (net (code "127") (name "Net-(RN5H-1)") (class "Default")
      (node (ref "RN5") (pin "8") (pinfunction "1_8") (pintype "passive"))
      (node (ref "U9") (pin "9") (pinfunction "OUT8_9") (pintype "open_collector"))
    )
    (net (code "128") (name "Net-(RN6B-1)") (class "Default")
      (node (ref "RN6") (pin "2") (pinfunction "1_2") (pintype "passive"))
      (node (ref "U10") (pin "15") (pinfunction "OUT2_15") (pintype "open_collector"))
    )
    (net (code "129") (name "Net-(RN6C-1)") (class "Default")
      (node (ref "RN6") (pin "3") (pinfunction "1_3") (pintype "passive"))
      (node (ref "U10") (pin "14") (pinfunction "OUT3_14") (pintype "open_collector"))
    )
    (net (code "130") (name "Net-(RN6C-2)") (class "Default")
      (node (ref "LED9") (pin "11") (pinfunction "C3_11") (pintype "output"))
      (node (ref "LED9") (pin "4") (pinfunction "C3_4") (pintype "output"))
      (node (ref "RN6") (pin "14") (pinfunction "2_14") (pintype "passive"))
    )
    (net (code "131") (name "Net-(RN6D-1)") (class "Default")
      (node (ref "RN6") (pin "4") (pinfunction "1_4") (pintype "passive"))
      (node (ref "U10") (pin "13") (pinfunction "OUT4_13") (pintype "open_collector"))
    )
    (net (code "132") (name "Net-(RN6E-1)") (class "Default")
      (node (ref "RN6") (pin "5") (pinfunction "1_5") (pintype "passive"))
      (node (ref "U10") (pin "12") (pinfunction "OUT5_12") (pintype "open_collector"))
    )
    (net (code "133") (name "Net-(RN6F-1)") (class "Default")
      (node (ref "RN6") (pin "6") (pinfunction "1_6") (pintype "passive"))
      (node (ref "U10") (pin "11") (pinfunction "OUT6_11") (pintype "open_collector"))
    )
    (net (code "134") (name "Net-(RN6G-1)") (class "Default")
      (node (ref "RN6") (pin "7") (pinfunction "1_7") (pintype "passive"))
      (node (ref "U10") (pin "10") (pinfunction "OUT7_10") (pintype "open_collector"))
    )
    (net (code "135") (name "Net-(RN6H-1)") (class "Default")
      (node (ref "RN6") (pin "8") (pinfunction "1_8") (pintype "passive"))
      (node (ref "U10") (pin "9") (pinfunction "OUT8_9") (pintype "open_collector"))
    )
    (net (code "136") (name "Net-(RN6H-2)") (class "Default")
      (node (ref "LED10") (pin "11") (pinfunction "C3_11") (pintype "output"))
      (node (ref "LED10") (pin "4") (pinfunction "C3_4") (pintype "output"))
      (node (ref "RN6") (pin "9") (pinfunction "2_9") (pintype "passive"))
    )
    (net (code "137") (name "Net-(RN7B-1)") (class "Default")
      (node (ref "RN7") (pin "2") (pinfunction "1_2") (pintype "passive"))
      (node (ref "U11") (pin "15") (pinfunction "OUT2_15") (pintype "open_collector"))
    )
    (net (code "138") (name "Net-(RN7C-1)") (class "Default")
      (node (ref "RN7") (pin "3") (pinfunction "1_3") (pintype "passive"))
      (node (ref "U11") (pin "14") (pinfunction "OUT3_14") (pintype "open_collector"))
    )
    (net (code "139") (name "Net-(RN7D-1)") (class "Default")
      (node (ref "RN7") (pin "4") (pinfunction "1_4") (pintype "passive"))
      (node (ref "U11") (pin "13") (pinfunction "OUT4_13") (pintype "open_collector"))
    )
    (net (code "140") (name "Net-(RN7E-1)") (class "Default")
      (node (ref "RN7") (pin "5") (pinfunction "1_5") (pintype "passive"))
      (node (ref "U11") (pin "12") (pinfunction "OUT5_12") (pintype "open_collector"))
    )
    (net (code "141") (name "Net-(RN7E-2)") (class "Default")
      (node (ref "LED11") (pin "11") (pinfunction "C3_11") (pintype "output"))
      (node (ref "LED11") (pin "4") (pinfunction "C3_4") (pintype "output"))
      (node (ref "RN7") (pin "12") (pinfunction "2_12") (pintype "passive"))
    )
    (net (code "142") (name "Net-(RN7F-1)") (class "Default")
      (node (ref "RN7") (pin "6") (pinfunction "1_6") (pintype "passive"))
      (node (ref "U11") (pin "11") (pinfunction "OUT6_11") (pintype "open_collector"))
    )
    (net (code "143") (name "Net-(RN7G-1)") (class "Default")
      (node (ref "RN7") (pin "7") (pinfunction "1_7") (pintype "passive"))
      (node (ref "U11") (pin "10") (pinfunction "OUT7_10") (pintype "open_collector"))
    )
    (net (code "144") (name "Net-(RN7H-1)") (class "Default")
      (node (ref "RN7") (pin "8") (pinfunction "1_8") (pintype "passive"))
      (node (ref "U11") (pin "9") (pinfunction "OUT8_9") (pintype "open_collector"))
    )
    (net (code "145") (name "Net-(U5A-OUT1)") (class "Default")
      (node (ref "RN1") (pin "1") (pinfunction "1_1") (pintype "passive"))
      (node (ref "U5") (pin "16") (pinfunction "OUT1_16") (pintype "open_collector"))
    )
    (net (code "146") (name "Net-(U5A-SDO)") (class "Default")
      (node (ref "U5") (pin "5") (pinfunction "SDO_5") (pintype "output"))
      (node (ref "U6") (pin "2") (pinfunction "SDI_2") (pintype "input"))
    )
    (net (code "147") (name "Net-(U6A-OUT1)") (class "Default")
      (node (ref "RN2") (pin "1") (pinfunction "1_1") (pintype "passive"))
      (node (ref "U6") (pin "16") (pinfunction "OUT1_16") (pintype "open_collector"))
    )
    (net (code "148") (name "Net-(U6A-SDO)") (class "Default")
      (node (ref "U6") (pin "5") (pinfunction "SDO_5") (pintype "output"))
      (node (ref "U7") (pin "2") (pinfunction "SDI_2") (pintype "input"))
    )
    (net (code "149") (name "Net-(U7A-OUT1)") (class "Default")
      (node (ref "RN3") (pin "1") (pinfunction "1_1") (pintype "passive"))
      (node (ref "U7") (pin "16") (pinfunction "OUT1_16") (pintype "open_collector"))
    )
    (net (code "150") (name "Net-(U7A-SDO)") (class "Default")
      (node (ref "U7") (pin "5") (pinfunction "SDO_5") (pintype "output"))
      (node (ref "U8") (pin "2") (pinfunction "SDI_2") (pintype "input"))
    )
    (net (code "151") (name "Net-(U8A-OUT1)") (class "Default")
      (node (ref "RN4") (pin "1") (pinfunction "1_1") (pintype "passive"))
      (node (ref "U8") (pin "16") (pinfunction "OUT1_16") (pintype "open_collector"))
    )
    (net (code "152") (name "Net-(U8A-SDO)") (class "Default")
      (node (ref "U8") (pin "5") (pinfunction "SDO_5") (pintype "output"))
      (node (ref "U9") (pin "2") (pinfunction "SDI_2") (pintype "input"))
    )
    (net (code "153") (name "Net-(U9A-OUT1)") (class "Default")
      (node (ref "RN5") (pin "1") (pinfunction "1_1") (pintype "passive"))
      (node (ref "U9") (pin "16") (pinfunction "OUT1_16") (pintype "open_collector"))
    )
    (net (code "154") (name "Net-(U10A-CLK)") (class "Default")
      (node (ref "U10") (pin "1") (pinfunction "CLK_1") (pintype "input"))
      (node (ref "U11") (pin "1") (pinfunction "CLK_1") (pintype "input"))
      (node (ref "U12") (pin "1") (pinfunction "CLK_1") (pintype "input"))
      (node (ref "U13") (pin "8") (pinfunction "CLK_8") (pintype "input"))
      (node (ref "U2") (pin "3") (pinfunction "O_3") (pintype "output"))
      (node (ref "U4") (pin "12") (pinfunction "I0_12") (pintype "input"))
      (node (ref "U4") (pin "13") (pinfunction "I1_13") (pintype "input"))
      (node (ref "U5") (pin "1") (pinfunction "CLK_1") (pintype "input"))
      (node (ref "U6") (pin "1") (pinfunction "CLK_1") (pintype "input"))
      (node (ref "U7") (pin "1") (pinfunction "CLK_1") (pintype "input"))
      (node (ref "U8") (pin "1") (pinfunction "CLK_1") (pintype "input"))
      (node (ref "U9") (pin "1") (pinfunction "CLK_1") (pintype "input"))
    )
    (net (code "155") (name "Net-(U10A-OUT1)") (class "Default")
      (node (ref "RN6") (pin "1") (pinfunction "1_1") (pintype "passive"))
      (node (ref "U10") (pin "16") (pinfunction "OUT1_16") (pintype "open_collector"))
    )
    (net (code "156") (name "Net-(U10A-SDI)") (class "Default")
      (node (ref "U10") (pin "2") (pinfunction "SDI_2") (pintype "input"))
      (node (ref "U9") (pin "5") (pinfunction "SDO_5") (pintype "output"))
    )
    (net (code "157") (name "Net-(U10A-SDO)") (class "Default")
      (node (ref "U10") (pin "5") (pinfunction "SDO_5") (pintype "output"))
      (node (ref "U11") (pin "2") (pinfunction "SDI_2") (pintype "input"))
    )
    (net (code "158") (name "Net-(U10A-~{OE})") (class "Default")
      (node (ref "U10") (pin "7") (pinfunction "~{OE}_7") (pintype "input"))
      (node (ref "U11") (pin "7") (pinfunction "~{OE}_7") (pintype "input"))
      (node (ref "U12") (pin "7") (pinfunction "~{OE}_7") (pintype "input"))
      (node (ref "U2") (pin "6") (pinfunction "O_6") (pintype "output"))
      (node (ref "U4") (pin "10") (pinfunction "I1_10") (pintype "input"))
      (node (ref "U4") (pin "9") (pinfunction "I0_9") (pintype "input"))
      (node (ref "U5") (pin "7") (pinfunction "~{OE}_7") (pintype "input"))
      (node (ref "U6") (pin "7") (pinfunction "~{OE}_7") (pintype "input"))
      (node (ref "U7") (pin "7") (pinfunction "~{OE}_7") (pintype "input"))
      (node (ref "U8") (pin "7") (pinfunction "~{OE}_7") (pintype "input"))
      (node (ref "U9") (pin "7") (pinfunction "~{OE}_7") (pintype "input"))
    )
    (net (code "159") (name "Net-(U11A-OUT1)") (class "Default")
      (node (ref "RN7") (pin "1") (pinfunction "1_1") (pintype "passive"))
      (node (ref "U11") (pin "16") (pinfunction "OUT1_16") (pintype "open_collector"))
    )
    (net (code "160") (name "Net-(U11A-SDO)") (class "Default")
      (node (ref "U11") (pin "5") (pinfunction "SDO_5") (pintype "output"))
      (node (ref "U12") (pin "2") (pinfunction "SDI_2") (pintype "input"))
      (node (ref "U13") (pin "1") (pinfunction "A_1") (pintype "input"))
      (node (ref "U13") (pin "2") (pinfunction "B_2") (pintype "input"))
    )
    (net (code "161") (name "Net-(U12A-OUT1)") (class "Default")
      (node (ref "R5") (pin "1") (pinfunction "1_1") (pintype "passive"))
      (node (ref "U12") (pin "16") (pinfunction "OUT1_16") (pintype "open_collector"))
    )
    (net (code "162") (name "Net-(U12A-OUT2)") (class "Default")
      (node (ref "R6") (pin "1") (pinfunction "1_1") (pintype "passive"))
      (node (ref "U12") (pin "15") (pinfunction "OUT2_15") (pintype "open_collector"))
    )
    (net (code "163") (name "Net-(U12A-OUT3)") (class "Default")
      (node (ref "R7") (pin "1") (pinfunction "1_1") (pintype "passive"))
      (node (ref "U12") (pin "14") (pinfunction "OUT3_14") (pintype "open_collector"))
    )
    (net (code "164") (name "Net-(U12A-OUT4)") (class "Default")
      (node (ref "R8") (pin "1") (pinfunction "1_1") (pintype "passive"))
      (node (ref "U12") (pin "13") (pinfunction "OUT4_13") (pintype "open_collector"))
    )
    (net (code "165") (name "Net-(U13A-QD)") (class "Default")
      (node (ref "U13") (pin "6") (pinfunction "QD_6") (pintype "output"))
      (node (ref "U4") (pin "4") (pinfunction "I0_4") (pintype "input"))
      (node (ref "U4") (pin "5") (pinfunction "I1_5") (pintype "input"))
    )
    (net (code "166") (name "unconnected-(INJ-KL-Pad5)") (class "Default")
      (node (ref "IN") (pin "5") (pinfunction "KL_5") (pintype "passive"))
    )
    (net (code "167") (name "unconnected-(OUTB-KL-Pad10)") (class "Default")
      (node (ref "OUT") (pin "10") (pinfunction "KL_10") (pintype "passive"))
    )
    (net (code "168") (name "unconnected-(OUTK-KL-Pad6)") (class "Default")
      (node (ref "OUT") (pin "6") (pinfunction "KL_6") (pintype "passive"))
    )
    (net (code "169") (name "unconnected-(OUT_BLB-KL-Pad10)") (class "Default")
      (node (ref "OUT_BL") (pin "10") (pinfunction "KL_10") (pintype "passive"))
    )
    (net (code "170") (name "unconnected-(OUT_BLM-KL-Pad8)") (class "Default")
      (node (ref "OUT_BL") (pin "8") (pinfunction "KL_8") (pintype "passive"))
    )
    (net (code "171") (name "unconnected-(OUT_BRB-KL-Pad10)") (class "Default")
      (node (ref "OUT_BR") (pin "10") (pinfunction "KL_10") (pintype "passive"))
    )
    (net (code "172") (name "unconnected-(OUT_BRM-KL-Pad8)") (class "Default")
      (node (ref "OUT_BR") (pin "8") (pinfunction "KL_8") (pintype "passive"))
    )
    (net (code "173") (name "unconnected-(U1A-8D-Pad18)") (class "Default")
      (node (ref "U1") (pin "18") (pinfunction "8D_18") (pintype "input"))
    )
    (net (code "174") (name "unconnected-(U1A-8Q-Pad19)") (class "Default")
      (node (ref "U1") (pin "19") (pinfunction "8Q_19") (pintype "tri_state"))
    )
    (net (code "175") (name "unconnected-(U2D-I0-Pad12)") (class "Default")
      (node (ref "U2") (pin "12") (pinfunction "I0_12") (pintype "input"))
    )
    (net (code "176") (name "unconnected-(U2D-I1-Pad13)") (class "Default")
      (node (ref "U2") (pin "13") (pinfunction "I1_13") (pintype "input"))
    )
    (net (code "177") (name "unconnected-(U2D-O-Pad11)") (class "Default")
      (node (ref "U2") (pin "11") (pinfunction "O_11") (pintype "output"))
    )
    (net (code "178") (name "unconnected-(U3-CD+-Pad10)") (class "Default")
      (node (ref "U3") (pin "10") (pinfunction "CD+_10") (pintype "passive"))
    )
    (net (code "179") (name "unconnected-(U3-I8-Pad8)") (class "Default")
      (node (ref "U3") (pin "8") (pinfunction "I8_8") (pintype "input"))
    )
    (net (code "180") (name "unconnected-(U3-O2-Pad17)") (class "Default")
      (node (ref "U3") (pin "17") (pinfunction "O2_17") (pintype "open_collector"))
    )
    (net (code "181") (name "unconnected-(U3-O3-Pad16)") (class "Default")
      (node (ref "U3") (pin "16") (pinfunction "O3_16") (pintype "open_collector"))
    )
    (net (code "182") (name "unconnected-(U3-O4-Pad15)") (class "Default")
      (node (ref "U3") (pin "15") (pinfunction "O4_15") (pintype "open_collector"))
    )
    (net (code "183") (name "unconnected-(U3-O5-Pad14)") (class "Default")
      (node (ref "U3") (pin "14") (pinfunction "O5_14") (pintype "open_collector"))
    )
    (net (code "184") (name "unconnected-(U3-O6-Pad13)") (class "Default")
      (node (ref "U3") (pin "13") (pinfunction "O6_13") (pintype "open_collector"))
    )
    (net (code "185") (name "unconnected-(U3-O7-Pad12)") (class "Default")
      (node (ref "U3") (pin "12") (pinfunction "O7_12") (pintype "open_collector"))
    )
    (net (code "186") (name "unconnected-(U3-O8-Pad11)") (class "Default")
      (node (ref "U3") (pin "11") (pinfunction "O8_11") (pintype "open_collector"))
    )
    (net (code "187") (name "unconnected-(U12A-OUT5-Pad12)") (class "Default")
      (node (ref "U12") (pin "12") (pinfunction "OUT5_12") (pintype "open_collector"))
    )
    (net (code "188") (name "unconnected-(U12A-OUT6-Pad11)") (class "Default")
      (node (ref "U12") (pin "11") (pinfunction "OUT6_11") (pintype "open_collector"))
    )
    (net (code "189") (name "unconnected-(U12A-OUT7-Pad10)") (class "Default")
      (node (ref "U12") (pin "10") (pinfunction "OUT7_10") (pintype "open_collector"))
    )
    (net (code "190") (name "unconnected-(U12A-OUT8-Pad9)") (class "Default")
      (node (ref "U12") (pin "9") (pinfunction "OUT8_9") (pintype "open_collector"))
    )
    (net (code "191") (name "unconnected-(U12A-SDO-Pad5)") (class "Default")
      (node (ref "U12") (pin "5") (pinfunction "SDO_5") (pintype "output"))
    )
    (net (code "192") (name "unconnected-(U13A-QA-Pad3)") (class "Default")
      (node (ref "U13") (pin "3") (pinfunction "QA_3") (pintype "output"))
    )
    (net (code "193") (name "unconnected-(U13A-QB-Pad4)") (class "Default")
      (node (ref "U13") (pin "4") (pinfunction "QB_4") (pintype "output"))
    )
    (net (code "194") (name "unconnected-(U13A-QC-Pad5)") (class "Default")
      (node (ref "U13") (pin "5") (pinfunction "QC_5") (pintype "output"))
    )
    (net (code "195") (name "unconnected-(U13A-QE-Pad10)") (class "Default")
      (node (ref "U13") (pin "10") (pinfunction "QE_10") (pintype "output"))
    )
    (net (code "196") (name "unconnected-(U13A-QF-Pad11)") (class "Default")
      (node (ref "U13") (pin "11") (pinfunction "QF_11") (pintype "output"))
    )
    (net (code "197") (name "unconnected-(U13A-QG-Pad12)") (class "Default")
      (node (ref "U13") (pin "12") (pinfunction "QG_12") (pintype "output"))
    )
    (net (code "198") (name "unconnected-(U13A-QH-Pad13)") (class "Default")
      (node (ref "U13") (pin "13") (pinfunction "QH_13") (pintype "output"))
    )
  )
)
